# Branly_Pi_v4.net
KiCad netlist of a schematic drawn in EAGLE
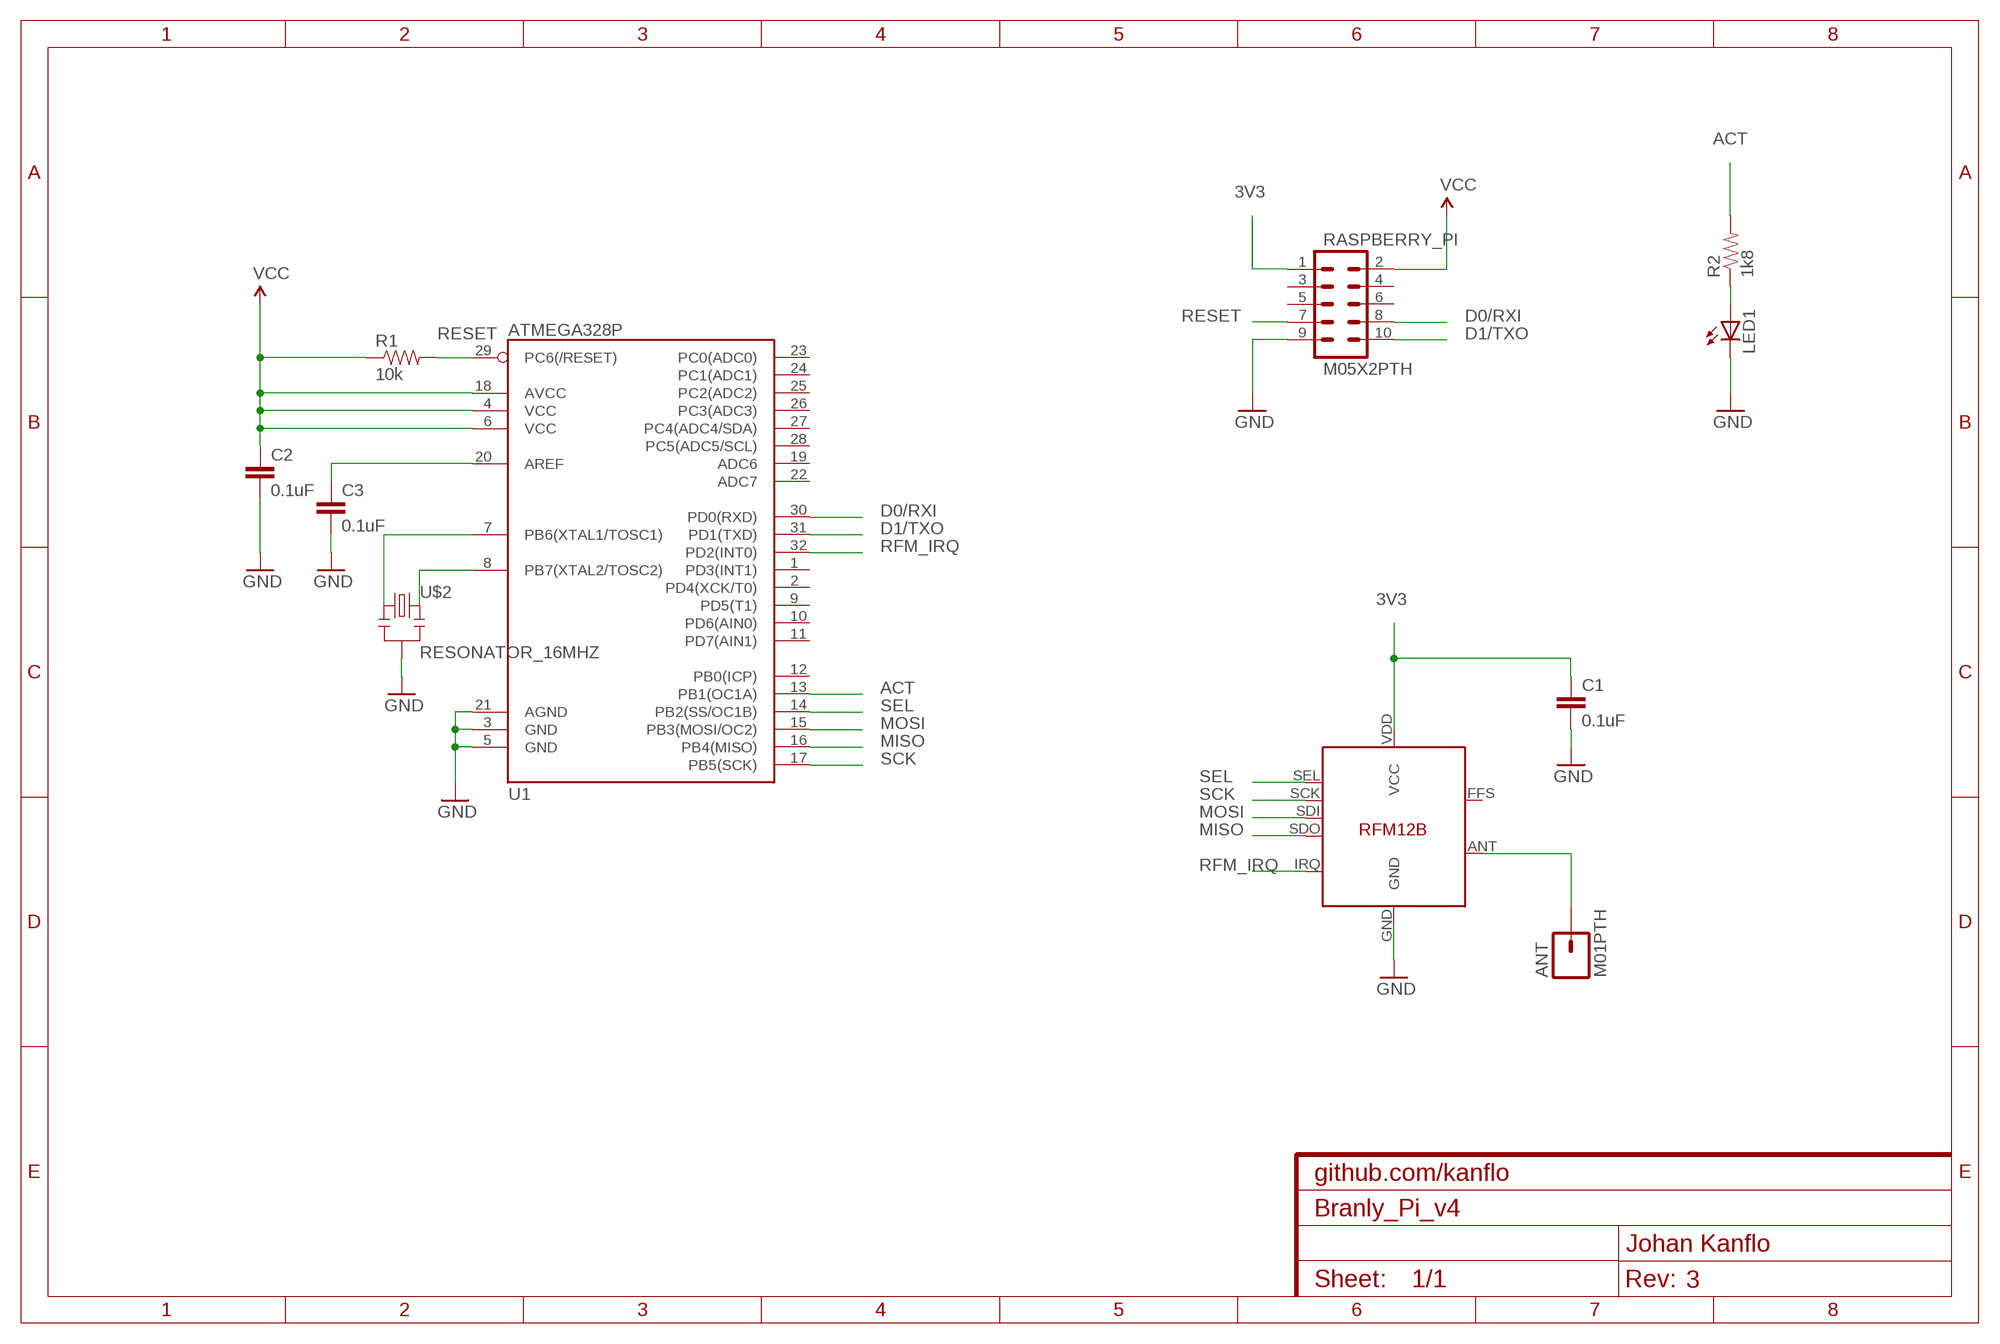
[diagram p0: schematic, sheet 1]

(export (version "E")
  (design (tool "Eeschema 10.0.6"))
  (components
    (comp (ref "ANT")
      (value "M01PTH")
      (footprint "eagle-import:1X01")
      (libsource (lib "eagle-import") (part "M01PTH"))
    )
    (comp (ref "C1")
      (value "0.1uF")
      (footprint "eagle-import:0603-CAP")
      (libsource (lib "eagle-import") (part "0.1UF-25V(+80/-20%)(0603)"))
    )
    (comp (ref "C2")
      (value "0.1uF")
      (footprint "eagle-import:0603-CAP")
      (libsource (lib "eagle-import") (part "0.1UF-25V(+80/-20%)(0603)"))
    )
    (comp (ref "C3")
      (value "0.1uF")
      (footprint "eagle-import:0603-CAP")
      (libsource (lib "eagle-import") (part "0.1UF-25V(+80/-20%)(0603)"))
    )
    (comp (ref "LED1")
      (value "LED0603")
      (footprint "eagle-import:LED-0603")
      (libsource (lib "eagle-import") (part "LED0603"))
    )
    (comp (ref "R1")
      (value "10k")
      (footprint "eagle-import:0603-RES")
      (libsource (lib "eagle-import") (part "RESISTOR0603-RES"))
    )
    (comp (ref "R2")
      (value "1k8")
      (footprint "eagle-import:0603-RES")
      (libsource (lib "eagle-import") (part "RESISTOR0603-RES"))
    )
    (comp (ref "RASPBERRY_PI")
      (value "M05X2PTH")
      (footprint "eagle-import:AVR_ICSP")
      (libsource (lib "eagle-import") (part "M05X2PTH"))
    )
    (comp (ref "U$2")
      (value "RESONATOR_16MHZ")
      (footprint "eagle-import:RESONATOR_SMD")
      (libsource (lib "eagle-import") (part "RESONATOR_16MHZ"))
    )
    (comp (ref "U1")
      (value "ATMEGA328P")
      (footprint "eagle-import:TQFP32-08")
      (libsource (lib "eagle-import") (part "ATMEGA328_SMT"))
    )
    (comp (ref "U2")
      (value "RFM12B")
      (footprint "eagle-import:RFM12B")
      (libsource (lib "eagle-import") (part "RFM12B"))
    )
  )
  (nets
    (net (code "1") (name "/3V3") (class "Default")
      (node (ref "C1") (pin "1") (pinfunction "1_1") (pintype "passive"))
      (node (ref "RASPBERRY_PI") (pin "1") (pinfunction "1_1") (pintype "passive"))
      (node (ref "U2") (pin "VDD") (pinfunction "VCC_VDD") (pintype "power_in"))
    )
    (net (code "2") (name "/ACT") (class "Default")
      (node (ref "R2") (pin "2") (pinfunction "2_2") (pintype "passive"))
      (node (ref "U1") (pin "13") (pinfunction "PB1(OC1A)_13") (pintype "bidirectional"))
    )
    (net (code "3") (name "/D0{slash}RXI") (class "Default")
      (node (ref "RASPBERRY_PI") (pin "8") (pinfunction "8_8") (pintype "passive"))
      (node (ref "U1") (pin "30") (pinfunction "PD0(RXD)_30") (pintype "bidirectional"))
    )
    (net (code "4") (name "/D1{slash}TXO") (class "Default")
      (node (ref "RASPBERRY_PI") (pin "10") (pinfunction "10_10") (pintype "passive"))
      (node (ref "U1") (pin "31") (pinfunction "PD1(TXD)_31") (pintype "bidirectional"))
    )
    (net (code "5") (name "/MISO") (class "Default")
      (node (ref "U1") (pin "16") (pinfunction "PB4(MISO)_16") (pintype "bidirectional"))
      (node (ref "U2") (pin "SDO") (pinfunction "SDO_SDO") (pintype "output"))
    )
    (net (code "6") (name "/MOSI") (class "Default")
      (node (ref "U1") (pin "15") (pinfunction "PB3(MOSI/OC2)_15") (pintype "bidirectional"))
      (node (ref "U2") (pin "SDI") (pinfunction "SDI_SDI") (pintype "input"))
    )
    (net (code "7") (name "/RESET") (class "Default")
      (node (ref "R1") (pin "2") (pinfunction "2_2") (pintype "passive"))
      (node (ref "RASPBERRY_PI") (pin "7") (pinfunction "7_7") (pintype "passive"))
      (node (ref "U1") (pin "29") (pinfunction "PC6(/RESET)_29") (pintype "bidirectional"))
    )
    (net (code "8") (name "/RFM_IRQ") (class "Default")
      (node (ref "U1") (pin "32") (pinfunction "PD2(INT0)_32") (pintype "bidirectional"))
      (node (ref "U2") (pin "IRQ") (pinfunction "IRQ_IRQ") (pintype "open_collector"))
    )
    (net (code "9") (name "/SCK") (class "Default")
      (node (ref "U1") (pin "17") (pinfunction "PB5(SCK)_17") (pintype "bidirectional"))
      (node (ref "U2") (pin "SCK") (pinfunction "SCK_SCK") (pintype "input"))
    )
    (net (code "10") (name "/SEL") (class "Default")
      (node (ref "U1") (pin "14") (pinfunction "PB2(SS/OC1B)_14") (pintype "bidirectional"))
      (node (ref "U2") (pin "SEL") (pinfunction "SEL_SEL") (pintype "input"))
    )
    (net (code "11") (name "GND") (class "Default")
      (node (ref "C1") (pin "2") (pinfunction "2_2") (pintype "passive"))
      (node (ref "C2") (pin "2") (pinfunction "2_2") (pintype "passive"))
      (node (ref "C3") (pin "2") (pinfunction "2_2") (pintype "passive"))
      (node (ref "LED1") (pin "C") (pinfunction "C_C") (pintype "passive"))
      (node (ref "RASPBERRY_PI") (pin "9") (pinfunction "9_9") (pintype "passive"))
      (node (ref "U$2") (pin "2") (pinfunction "2_2") (pintype "passive"))
      (node (ref "U1") (pin "21") (pinfunction "AGND_21") (pintype "bidirectional"))
      (node (ref "U1") (pin "3") (pinfunction "GND_3") (pintype "bidirectional"))
      (node (ref "U1") (pin "5") (pinfunction "GND_5") (pintype "bidirectional"))
      (node (ref "U2") (pin "GND") (pinfunction "GND_GND") (pintype "power_in"))
    )
    (net (code "12") (name "Net-(ANT-Pad1)") (class "Default")
      (node (ref "ANT") (pin "1") (pinfunction "1_1") (pintype "passive"))
      (node (ref "U2") (pin "ANT") (pinfunction "ANT_ANT") (pintype "passive"))
    )
    (net (code "13") (name "Net-(LED1-PadA)") (class "Default")
      (node (ref "LED1") (pin "A") (pinfunction "A_A") (pintype "passive"))
      (node (ref "R2") (pin "1") (pinfunction "1_1") (pintype "passive"))
    )
    (net (code "14") (name "Net-(U1-AREF)") (class "Default")
      (node (ref "C3") (pin "1") (pinfunction "1_1") (pintype "passive"))
      (node (ref "U1") (pin "20") (pinfunction "AREF_20") (pintype "bidirectional"))
    )
    (net (code "15") (name "Net-(U1-PB6(XTAL1{slash}TOSC1))") (class "Default")
      (node (ref "U$2") (pin "1") (pinfunction "1_1") (pintype "passive"))
      (node (ref "U1") (pin "7") (pinfunction "PB6(XTAL1/TOSC1)_7") (pintype "bidirectional"))
    )
    (net (code "16") (name "Net-(U1-PB7(XTAL2{slash}TOSC2))") (class "Default")
      (node (ref "U$2") (pin "3") (pinfunction "3_3") (pintype "passive"))
      (node (ref "U1") (pin "8") (pinfunction "PB7(XTAL2/TOSC2)_8") (pintype "bidirectional"))
    )
    (net (code "17") (name "VCC") (class "Default")
      (node (ref "C2") (pin "1") (pinfunction "1_1") (pintype "passive"))
      (node (ref "R1") (pin "1") (pinfunction "1_1") (pintype "passive"))
      (node (ref "RASPBERRY_PI") (pin "2") (pinfunction "2_2") (pintype "passive"))
      (node (ref "U1") (pin "18") (pinfunction "AVCC_18") (pintype "bidirectional"))
      (node (ref "U1") (pin "4") (pinfunction "VCC_4") (pintype "bidirectional"))
      (node (ref "U1") (pin "6") (pinfunction "VCC_6") (pintype "bidirectional"))
    )
    (net (code "18") (name "unconnected-(RASPBERRY_PI-Pad3)") (class "Default")
      (node (ref "RASPBERRY_PI") (pin "3") (pinfunction "3_3") (pintype "passive"))
    )
    (net (code "19") (name "unconnected-(RASPBERRY_PI-Pad4)") (class "Default")
      (node (ref "RASPBERRY_PI") (pin "4") (pinfunction "4_4") (pintype "passive"))
    )
    (net (code "20") (name "unconnected-(RASPBERRY_PI-Pad5)") (class "Default")
      (node (ref "RASPBERRY_PI") (pin "5") (pinfunction "5_5") (pintype "passive"))
    )
    (net (code "21") (name "unconnected-(RASPBERRY_PI-Pad6)") (class "Default")
      (node (ref "RASPBERRY_PI") (pin "6") (pinfunction "6_6") (pintype "passive"))
    )
    (net (code "22") (name "unconnected-(U1-ADC6-Pad19)") (class "Default")
      (node (ref "U1") (pin "19") (pinfunction "ADC6_19") (pintype "bidirectional"))
    )
    (net (code "23") (name "unconnected-(U1-ADC7-Pad22)") (class "Default")
      (node (ref "U1") (pin "22") (pinfunction "ADC7_22") (pintype "bidirectional"))
    )
    (net (code "24") (name "unconnected-(U1-PB0(ICP)-Pad12)") (class "Default")
      (node (ref "U1") (pin "12") (pinfunction "PB0(ICP)_12") (pintype "bidirectional"))
    )
    (net (code "25") (name "unconnected-(U1-PC0(ADC0)-Pad23)") (class "Default")
      (node (ref "U1") (pin "23") (pinfunction "PC0(ADC0)_23") (pintype "bidirectional"))
    )
    (net (code "26") (name "unconnected-(U1-PC1(ADC1)-Pad24)") (class "Default")
      (node (ref "U1") (pin "24") (pinfunction "PC1(ADC1)_24") (pintype "bidirectional"))
    )
    (net (code "27") (name "unconnected-(U1-PC2(ADC2)-Pad25)") (class "Default")
      (node (ref "U1") (pin "25") (pinfunction "PC2(ADC2)_25") (pintype "bidirectional"))
    )
    (net (code "28") (name "unconnected-(U1-PC3(ADC3)-Pad26)") (class "Default")
      (node (ref "U1") (pin "26") (pinfunction "PC3(ADC3)_26") (pintype "bidirectional"))
    )
    (net (code "29") (name "unconnected-(U1-PC4(ADC4{slash}SDA)-Pad27)") (class "Default")
      (node (ref "U1") (pin "27") (pinfunction "PC4(ADC4/SDA)_27") (pintype "bidirectional"))
    )
    (net (code "30") (name "unconnected-(U1-PC5(ADC5{slash}SCL)-Pad28)") (class "Default")
      (node (ref "U1") (pin "28") (pinfunction "PC5(ADC5/SCL)_28") (pintype "bidirectional"))
    )
    (net (code "31") (name "unconnected-(U1-PD3(INT1)-Pad1)") (class "Default")
      (node (ref "U1") (pin "1") (pinfunction "PD3(INT1)_1") (pintype "bidirectional"))
    )
    (net (code "32") (name "unconnected-(U1-PD4(XCK{slash}T0)-Pad2)") (class "Default")
      (node (ref "U1") (pin "2") (pinfunction "PD4(XCK/T0)_2") (pintype "bidirectional"))
    )
    (net (code "33") (name "unconnected-(U1-PD5(T1)-Pad9)") (class "Default")
      (node (ref "U1") (pin "9") (pinfunction "PD5(T1)_9") (pintype "bidirectional"))
    )
    (net (code "34") (name "unconnected-(U1-PD6(AIN0)-Pad10)") (class "Default")
      (node (ref "U1") (pin "10") (pinfunction "PD6(AIN0)_10") (pintype "bidirectional"))
    )
    (net (code "35") (name "unconnected-(U1-PD7(AIN1)-Pad11)") (class "Default")
      (node (ref "U1") (pin "11") (pinfunction "PD7(AIN1)_11") (pintype "bidirectional"))
    )
    (net (code "36") (name "unconnected-(U2-PadFFS)") (class "Default")
      (node (ref "U2") (pin "FFS") (pinfunction "FFS_FFS") (pintype "bidirectional"))
    )
  )
)
